# MIDDLE_LAYER.net
KiCad netlist of a schematic drawn in Altium Designer
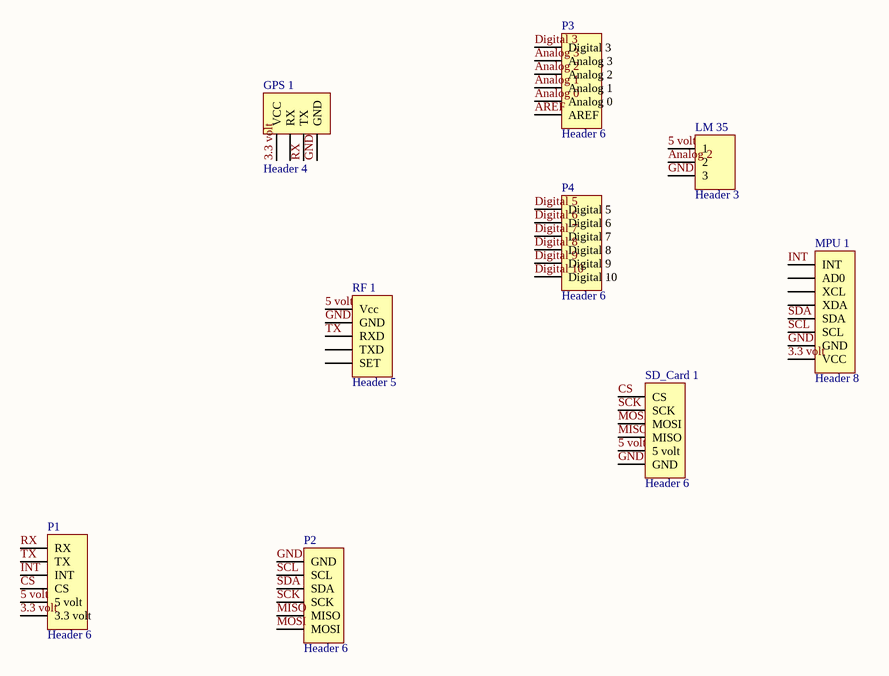
[diagram p0: MIDDLE LAYER.SchDoc]

(export (version "E")
  (design (tool "Eeschema 10.0.6"))
  (components
    (comp (ref "GPS 1")
      (value "Header 4")
      (footprint "HDR1X4")
      (description "Header, 4-Pin")
      (fields (field (name "PUBLISHER") "Altium Limited"))
      (libsource (lib "Miscellaneous Connectors") (part "Header 4"))
    )
    (comp (ref "LM 35")
      (value "Header 3")
      (footprint "HDR1X3")
      (description "Header, 3-Pin")
      (fields (field (name "PUBLISHER") "Altium Limited"))
      (libsource (lib "Miscellaneous Connectors") (part "Header 3"))
    )
    (comp (ref "MPU 1")
      (value "Header 8")
      (footprint "HDR1X8")
      (description "Header, 8-Pin")
      (fields (field (name "PUBLISHER") "Altium Limited"))
      (libsource (lib "Miscellaneous Connectors") (part "Header 8"))
    )
    (comp (ref "P1")
      (value "Header 6")
      (footprint "HDR1X6")
      (description "Header, 6-Pin")
      (fields (field (name "PUBLISHER") "Altium Limited"))
      (libsource (lib "Miscellaneous Connectors") (part "Header 6"))
    )
    (comp (ref "P2")
      (value "Header 6")
      (footprint "HDR1X6")
      (description "Header, 6-Pin")
      (fields (field (name "PUBLISHER") "Altium Limited"))
      (libsource (lib "Miscellaneous Connectors") (part "Header 6"))
    )
    (comp (ref "P3")
      (value "Header 6")
      (footprint "HDR1X6")
      (description "Header, 6-Pin")
      (fields (field (name "PUBLISHER") "Altium Limited"))
      (libsource (lib "Miscellaneous Connectors") (part "Header 6"))
    )
    (comp (ref "P4")
      (value "Header 6")
      (footprint "HDR1X6")
      (description "Header, 6-Pin")
      (fields (field (name "PUBLISHER") "Altium Limited"))
      (libsource (lib "Miscellaneous Connectors") (part "Header 6"))
    )
    (comp (ref "RF 1")
      (value "Header 5")
      (footprint "HDR1X5")
      (description "Header, 5-Pin")
      (fields (field (name "PUBLISHER") "Altium Limited"))
      (libsource (lib "Miscellaneous Connectors") (part "Header 5"))
    )
    (comp (ref "SD_Card 1")
      (value "Header 6")
      (footprint "HDR1X6")
      (description "Header, 6-Pin")
      (fields (field (name "PUBLISHER") "Altium Limited"))
      (libsource (lib "Miscellaneous Connectors") (part "Header 6"))
    )
  )
  (nets
    (net (code "1") (name "/3.3 volt") (class "Default")
      (node (ref "GPS 1") (pin "1") (pinfunction "VCC_1") (pintype "passive"))
      (node (ref "MPU 1") (pin "8") (pinfunction "VCC_8") (pintype "passive"))
      (node (ref "P1") (pin "6") (pinfunction "3.3_volt_6") (pintype "passive"))
    )
    (net (code "2") (name "/5 volt") (class "Default")
      (node (ref "LM 35") (pin "1") (pinfunction "1_1") (pintype "passive"))
      (node (ref "P1") (pin "5") (pinfunction "5_volt_5") (pintype "passive"))
      (node (ref "RF 1") (pin "1") (pinfunction "Vcc_1") (pintype "passive"))
      (node (ref "SD_Card 1") (pin "5") (pinfunction "5_volt_5") (pintype "passive"))
    )
    (net (code "3") (name "/AREF") (class "Default")
      (node (ref "P3") (pin "6") (pinfunction "3.3_volt_6") (pintype "passive"))
    )
    (net (code "4") (name "/Analog 0") (class "Default")
      (node (ref "P3") (pin "5") (pinfunction "5_volt_5") (pintype "passive"))
    )
    (net (code "5") (name "/Analog 1") (class "Default")
      (node (ref "P3") (pin "4") (pinfunction "CS_4") (pintype "passive"))
    )
    (net (code "6") (name "/Analog 2") (class "Default")
      (node (ref "LM 35") (pin "2") (pinfunction "2_2") (pintype "passive"))
      (node (ref "P3") (pin "3") (pinfunction "INT_3") (pintype "passive"))
    )
    (net (code "7") (name "/Analog 3") (class "Default")
      (node (ref "P3") (pin "2") (pinfunction "TX_2") (pintype "passive"))
    )
    (net (code "8") (name "/CS") (class "Default")
      (node (ref "P1") (pin "4") (pinfunction "CS_4") (pintype "passive"))
      (node (ref "SD_Card 1") (pin "1") (pinfunction "RX_1") (pintype "passive"))
    )
    (net (code "9") (name "/Digital 3") (class "Default")
      (node (ref "P3") (pin "1") (pinfunction "RX_1") (pintype "passive"))
    )
    (net (code "10") (name "/Digital 5") (class "Default")
      (node (ref "P4") (pin "1") (pinfunction "RX_1") (pintype "passive"))
    )
    (net (code "11") (name "/Digital 6") (class "Default")
      (node (ref "P4") (pin "2") (pinfunction "TX_2") (pintype "passive"))
    )
    (net (code "12") (name "/Digital 7") (class "Default")
      (node (ref "P4") (pin "3") (pinfunction "INT_3") (pintype "passive"))
    )
    (net (code "13") (name "/Digital 8") (class "Default")
      (node (ref "P4") (pin "4") (pinfunction "CS_4") (pintype "passive"))
    )
    (net (code "14") (name "/Digital 9") (class "Default")
      (node (ref "P4") (pin "5") (pinfunction "5_volt_5") (pintype "passive"))
    )
    (net (code "15") (name "/Digital 10") (class "Default")
      (node (ref "P4") (pin "6") (pinfunction "3.3_volt_6") (pintype "passive"))
    )
    (net (code "16") (name "/GND") (class "Default")
      (node (ref "GPS 1") (pin "4") (pinfunction "GND_4") (pintype "passive"))
      (node (ref "LM 35") (pin "3") (pinfunction "3_3") (pintype "passive"))
      (node (ref "MPU 1") (pin "7") (pinfunction "GND_7") (pintype "passive"))
      (node (ref "P2") (pin "1") (pinfunction "RX_1") (pintype "passive"))
      (node (ref "RF 1") (pin "2") (pinfunction "GND_2") (pintype "passive"))
      (node (ref "SD_Card 1") (pin "6") (pinfunction "3.3_volt_6") (pintype "passive"))
    )
    (net (code "17") (name "/INT") (class "Default")
      (node (ref "MPU 1") (pin "1") (pinfunction "INT_1") (pintype "passive"))
      (node (ref "P1") (pin "3") (pinfunction "INT_3") (pintype "passive"))
    )
    (net (code "18") (name "/MISO") (class "Default")
      (node (ref "P2") (pin "5") (pinfunction "5_volt_5") (pintype "passive"))
      (node (ref "SD_Card 1") (pin "4") (pinfunction "CS_4") (pintype "passive"))
    )
    (net (code "19") (name "/MOSI") (class "Default")
      (node (ref "P2") (pin "6") (pinfunction "3.3_volt_6") (pintype "passive"))
      (node (ref "SD_Card 1") (pin "3") (pinfunction "INT_3") (pintype "passive"))
    )
    (net (code "20") (name "/RX") (class "Default")
      (node (ref "GPS 1") (pin "3") (pinfunction "TX_3") (pintype "passive"))
      (node (ref "P1") (pin "1") (pinfunction "RX_1") (pintype "passive"))
    )
    (net (code "21") (name "/SCK") (class "Default")
      (node (ref "P2") (pin "4") (pinfunction "CS_4") (pintype "passive"))
      (node (ref "SD_Card 1") (pin "2") (pinfunction "TX_2") (pintype "passive"))
    )
    (net (code "22") (name "/SCL") (class "Default")
      (node (ref "MPU 1") (pin "6") (pinfunction "SCL_6") (pintype "passive"))
      (node (ref "P2") (pin "2") (pinfunction "TX_2") (pintype "passive"))
    )
    (net (code "23") (name "/SDA") (class "Default")
      (node (ref "MPU 1") (pin "5") (pinfunction "SDA_5") (pintype "passive"))
      (node (ref "P2") (pin "3") (pinfunction "INT_3") (pintype "passive"))
    )
    (net (code "24") (name "/TX") (class "Default")
      (node (ref "P1") (pin "2") (pinfunction "TX_2") (pintype "passive"))
      (node (ref "RF 1") (pin "3") (pinfunction "RXD_3") (pintype "passive"))
    )
    (net (code "25") (name "unconnected-(GPS 1-RX-Pad2)") (class "Default")
      (node (ref "GPS 1") (pin "2") (pinfunction "RX_2") (pintype "passive"))
    )
    (net (code "26") (name "unconnected-(MPU 1-AD0-Pad2)") (class "Default")
      (node (ref "MPU 1") (pin "2") (pinfunction "AD0_2") (pintype "passive"))
    )
    (net (code "27") (name "unconnected-(MPU 1-XCL-Pad3)") (class "Default")
      (node (ref "MPU 1") (pin "3") (pinfunction "XCL_3") (pintype "passive"))
    )
    (net (code "28") (name "unconnected-(MPU 1-XDA-Pad4)") (class "Default")
      (node (ref "MPU 1") (pin "4") (pinfunction "XDA_4") (pintype "passive"))
    )
    (net (code "29") (name "unconnected-(RF 1-SET-Pad5)") (class "Default")
      (node (ref "RF 1") (pin "5") (pinfunction "SET_5") (pintype "passive"))
    )
    (net (code "30") (name "unconnected-(RF 1-TXD-Pad4)") (class "Default")
      (node (ref "RF 1") (pin "4") (pinfunction "TXD_4") (pintype "passive"))
    )
  )
)
